# DRV8432SchDoc.net
KiCad netlist of a schematic drawn in Altium Designer
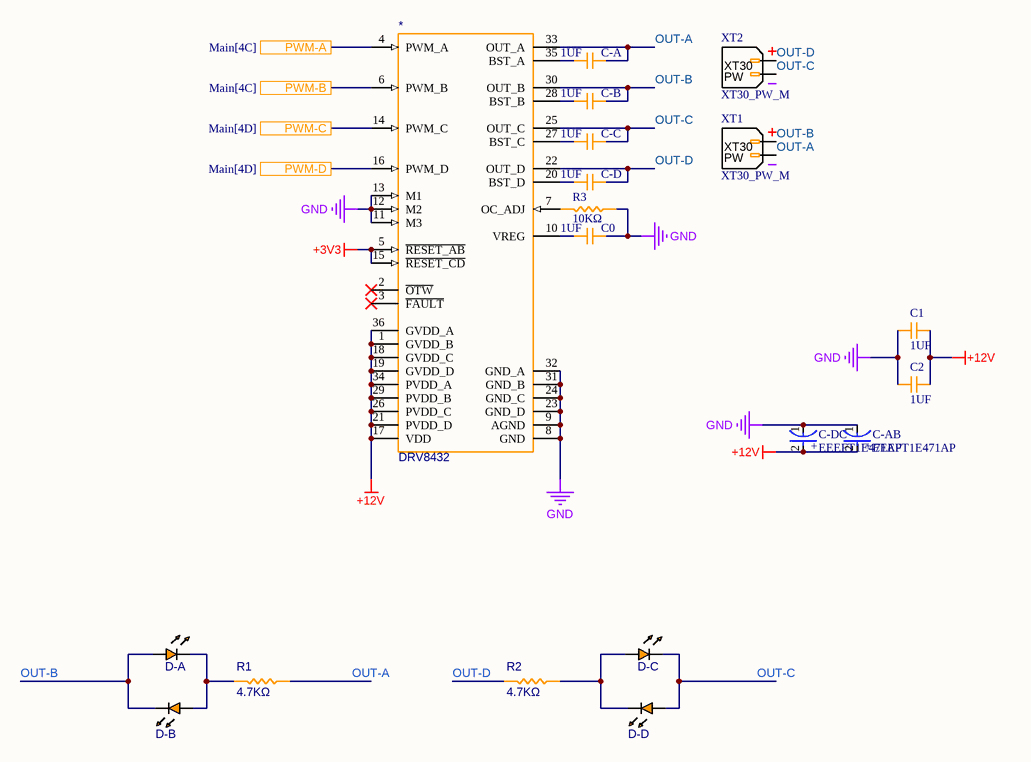
[diagram p0: DRV8432SchDoc.SchDoc]

(export (version "E")
  (design (tool "Eeschema 10.0.6"))
  (components
    (comp (ref "*") (value "DRV8432") (footprint "DRV8432") (libsource (lib "RC") (part "DRV8432")))
    (comp (ref "C-A")
      (value "1UF")
      (footprint "CAP_0603")
      (description "Capacitor SMD 0603 generic")
      (libsource (lib "RC") (part "CAP_0603"))
    )
    (comp (ref "C-AB")
      (value "EEEFT1E471AP")
      (footprint "FP-FTF-MFG")
      (description "CAP ALUM 470UF 20% 25V SMD")
      (fields (field (name "VOLTAGE") "25V") (field (name "TOLERANCE") "20%"))
      (libsource (lib "Altium Content Vault") (part "a00bbbee19879c290e62620ae7e47b1"))
    )
    (comp (ref "C-B")
      (value "1UF")
      (footprint "CAP_0603")
      (description "Capacitor SMD 0603 generic")
      (libsource (lib "RC") (part "CAP_0603"))
    )
    (comp (ref "C-C")
      (value "1UF")
      (footprint "CAP_0603")
      (description "Capacitor SMD 0603 generic")
      (libsource (lib "RC") (part "CAP_0603"))
    )
    (comp (ref "C-D")
      (value "1UF")
      (footprint "CAP_0603")
      (description "Capacitor SMD 0603 generic")
      (libsource (lib "RC") (part "CAP_0603"))
    )
    (comp (ref "C-DC")
      (value "EEEFT1E471AP")
      (footprint "FP-FTF-MFG")
      (description "CAP ALUM 470UF 20% 25V SMD")
      (fields (field (name "VOLTAGE") "25V") (field (name "TOLERANCE") "20%"))
      (libsource (lib "Altium Content Vault") (part "a00bbbee19879c290e62620ae7e47b1"))
    )
    (comp (ref "C0")
      (value "1UF")
      (footprint "CAP_0603")
      (description "Capacitor SMD 0603 generic")
      (libsource (lib "RC") (part "CAP_0603"))
    )
    (comp (ref "C1")
      (value "1UF")
      (footprint "CAP_0603")
      (description "Capacitor SMD 0603 generic")
      (libsource (lib "RC") (part "CAP_0603"))
    )
    (comp (ref "C2")
      (value "1UF")
      (footprint "CAP_0603")
      (description "Capacitor SMD 0603 generic")
      (libsource (lib "RC") (part "CAP_0603"))
    )
    (comp (ref "D-A")
      (value "LED_0603")
      (footprint "LED_0603")
      (libsource (lib "GenericRC") (part "LED_0603"))
    )
    (comp (ref "D-B")
      (value "LED_0603")
      (footprint "LED_0603")
      (libsource (lib "GenericRC") (part "LED_0603"))
    )
    (comp (ref "D-C")
      (value "LED_0603")
      (footprint "LED_0603")
      (libsource (lib "GenericRC") (part "LED_0603"))
    )
    (comp (ref "D-D")
      (value "LED_0603")
      (footprint "LED_0603")
      (libsource (lib "GenericRC") (part "LED_0603"))
    )
    (comp (ref "R1")
      (value "4.7KΩ")
      (footprint "RES_0603")
      (description "Resistor SMD 0603 generic")
      (libsource (lib "GenericRC") (part "RES_0603"))
    )
    (comp (ref "R2")
      (value "4.7KΩ")
      (footprint "RES_0603")
      (description "Resistor SMD 0603 generic")
      (libsource (lib "GenericRC") (part "RES_0603"))
    )
    (comp (ref "R3")
      (value "10KΩ")
      (footprint "RES_0603")
      (description "Resistor SMD 0603 generic")
      (libsource (lib "RC") (part "RES_0603"))
    )
    (comp (ref "XT1") (value "XT30_PW_M") (footprint "XT30_PW_M") (libsource (lib "RC") (part "XT30_PW_M")))
    (comp (ref "XT2") (value "XT30_PW_M") (footprint "XT30_PW_M") (libsource (lib "RC") (part "XT30_PW_M")))
  )
  (nets
    (net (code "1") (name "+3V3") (class "Default")
      (node (ref "*") (pin "15") (pinfunction "~{RESET_CD}_15") (pintype "input"))
      (node (ref "*") (pin "5") (pinfunction "~{RESET_AB}_5") (pintype "input"))
    )
    (net (code "2") (name "+12V") (class "Default")
      (node (ref "*") (pin "1") (pinfunction "GVDD_B_1") (pintype "power_in"))
      (node (ref "*") (pin "17") (pinfunction "VDD_17") (pintype "power_in"))
      (node (ref "*") (pin "18") (pinfunction "GVDD_C_18") (pintype "power_in"))
      (node (ref "*") (pin "19") (pinfunction "GVDD_D_19") (pintype "power_in"))
      (node (ref "*") (pin "21") (pinfunction "PVDD_D_21") (pintype "power_in"))
      (node (ref "*") (pin "26") (pinfunction "PVDD_C_26") (pintype "power_in"))
      (node (ref "*") (pin "29") (pinfunction "PVDD_B_29") (pintype "power_in"))
      (node (ref "*") (pin "34") (pinfunction "PVDD_A_34") (pintype "power_in"))
      (node (ref "*") (pin "36") (pinfunction "GVDD_A_36") (pintype "power_in"))
      (node (ref "C-AB") (pin "2") (pinfunction "A_2") (pintype "passive"))
      (node (ref "C-DC") (pin "2") (pinfunction "A_2") (pintype "passive"))
      (node (ref "C1") (pin "2") (pintype "passive"))
      (node (ref "C2") (pin "2") (pintype "passive"))
    )
    (net (code "3") (name "/OUT-A") (class "Default")
      (node (ref "*") (pin "33") (pinfunction "OUT_A_33") (pintype "tri_state"))
      (node (ref "C-A") (pin "2") (pintype "passive"))
      (node (ref "R1") (pin "2") (pintype "passive"))
      (node (ref "XT1") (pin "N") (pinfunction "N_N") (pintype "power_in"))
    )
    (net (code "4") (name "/OUT-B") (class "Default")
      (node (ref "*") (pin "30") (pinfunction "OUT_B_30") (pintype "tri_state"))
      (node (ref "C-B") (pin "2") (pintype "passive"))
      (node (ref "D-A") (pin "A") (pinfunction "2_A") (pintype "passive"))
      (node (ref "D-B") (pin "C") (pinfunction "1_C") (pintype "passive"))
      (node (ref "XT1") (pin "P") (pinfunction "P_P") (pintype "power_in"))
    )
    (net (code "5") (name "/OUT-C") (class "Default")
      (node (ref "*") (pin "25") (pinfunction "OUT_C_25") (pintype "tri_state"))
      (node (ref "C-C") (pin "2") (pintype "passive"))
      (node (ref "D-C") (pin "C") (pinfunction "1_C") (pintype "passive"))
      (node (ref "D-D") (pin "A") (pinfunction "2_A") (pintype "passive"))
      (node (ref "XT2") (pin "N") (pinfunction "N_N") (pintype "power_in"))
    )
    (net (code "6") (name "/OUT-D") (class "Default")
      (node (ref "*") (pin "22") (pinfunction "OUT_D_22") (pintype "tri_state"))
      (node (ref "C-D") (pin "2") (pintype "passive"))
      (node (ref "R2") (pin "1") (pintype "passive"))
      (node (ref "XT2") (pin "P") (pinfunction "P_P") (pintype "power_in"))
    )
    (net (code "7") (name "/PWM-A") (class "Default")
      (node (ref "*") (pin "4") (pinfunction "PWM_A_4") (pintype "input"))
    )
    (net (code "8") (name "/PWM-B") (class "Default")
      (node (ref "*") (pin "6") (pinfunction "PWM_B_6") (pintype "input"))
    )
    (net (code "9") (name "/PWM-C") (class "Default")
      (node (ref "*") (pin "14") (pinfunction "PWM_C_14") (pintype "input"))
    )
    (net (code "10") (name "/PWM-D") (class "Default")
      (node (ref "*") (pin "16") (pinfunction "PWM_D_16") (pintype "input"))
    )
    (net (code "11") (name "GND") (class "Default")
      (node (ref "*") (pin "11") (pinfunction "M3_11") (pintype "input"))
      (node (ref "*") (pin "12") (pinfunction "M2_12") (pintype "input"))
      (node (ref "*") (pin "13") (pinfunction "M1_13") (pintype "input"))
      (node (ref "*") (pin "23") (pinfunction "GND_D_23") (pintype "power_in"))
      (node (ref "*") (pin "24") (pinfunction "GND_C_24") (pintype "power_in"))
      (node (ref "*") (pin "31") (pinfunction "GND_B_31") (pintype "power_in"))
      (node (ref "*") (pin "32") (pinfunction "GND_A_32") (pintype "power_in"))
      (node (ref "*") (pin "8") (pinfunction "GND_8") (pintype "power_in"))
      (node (ref "*") (pin "9") (pinfunction "AGND_9") (pintype "power_in"))
      (node (ref "C-AB") (pin "1") (pinfunction "C_1") (pintype "passive"))
      (node (ref "C-DC") (pin "1") (pinfunction "C_1") (pintype "passive"))
      (node (ref "C0") (pin "2") (pintype "passive"))
      (node (ref "C1") (pin "1") (pintype "passive"))
      (node (ref "C2") (pin "1") (pintype "passive"))
      (node (ref "R3") (pin "2") (pintype "passive"))
    )
    (net (code "12") (name "Net-(*-BST_A)") (class "Default")
      (node (ref "*") (pin "35") (pinfunction "BST_A_35") (pintype "passive"))
      (node (ref "C-A") (pin "1") (pintype "passive"))
    )
    (net (code "13") (name "Net-(*-BST_B)") (class "Default")
      (node (ref "*") (pin "28") (pinfunction "BST_B_28") (pintype "passive"))
      (node (ref "C-B") (pin "1") (pintype "passive"))
    )
    (net (code "14") (name "Net-(*-BST_C)") (class "Default")
      (node (ref "*") (pin "27") (pinfunction "BST_C_27") (pintype "passive"))
      (node (ref "C-C") (pin "1") (pintype "passive"))
    )
    (net (code "15") (name "Net-(*-BST_D)") (class "Default")
      (node (ref "*") (pin "20") (pinfunction "BST_D_20") (pintype "passive"))
      (node (ref "C-D") (pin "1") (pintype "passive"))
    )
    (net (code "16") (name "Net-(*-OC_ADJ)") (class "Default")
      (node (ref "*") (pin "7") (pinfunction "OC_ADJ_7") (pintype "input"))
      (node (ref "R3") (pin "1") (pintype "passive"))
    )
    (net (code "17") (name "Net-(*-VREG)") (class "Default")
      (node (ref "*") (pin "10") (pinfunction "VREG_10") (pintype "passive"))
      (node (ref "C0") (pin "1") (pintype "passive"))
    )
    (net (code "18") (name "Net-(D-A-1)") (class "Default")
      (node (ref "D-A") (pin "C") (pinfunction "1_C") (pintype "passive"))
      (node (ref "D-B") (pin "A") (pinfunction "2_A") (pintype "passive"))
      (node (ref "R1") (pin "1") (pintype "passive"))
    )
    (net (code "19") (name "Net-(D-C-2)") (class "Default")
      (node (ref "D-C") (pin "A") (pinfunction "2_A") (pintype "passive"))
      (node (ref "D-D") (pin "C") (pinfunction "1_C") (pintype "passive"))
      (node (ref "R2") (pin "2") (pintype "passive"))
    )
    (net (code "20") (name "unconnected-(*-~{FAULT}-Pad3)") (class "Default")
      (node (ref "*") (pin "3") (pinfunction "~{FAULT}_3") (pintype "open_collector+no_connect"))
    )
    (net (code "21") (name "unconnected-(*-~{OTW}-Pad2)") (class "Default")
      (node (ref "*") (pin "2") (pinfunction "~{OTW}_2") (pintype "open_collector+no_connect"))
    )
  )
)
